# mini.net
KiCad netlist of a schematic drawn in Altium Designer
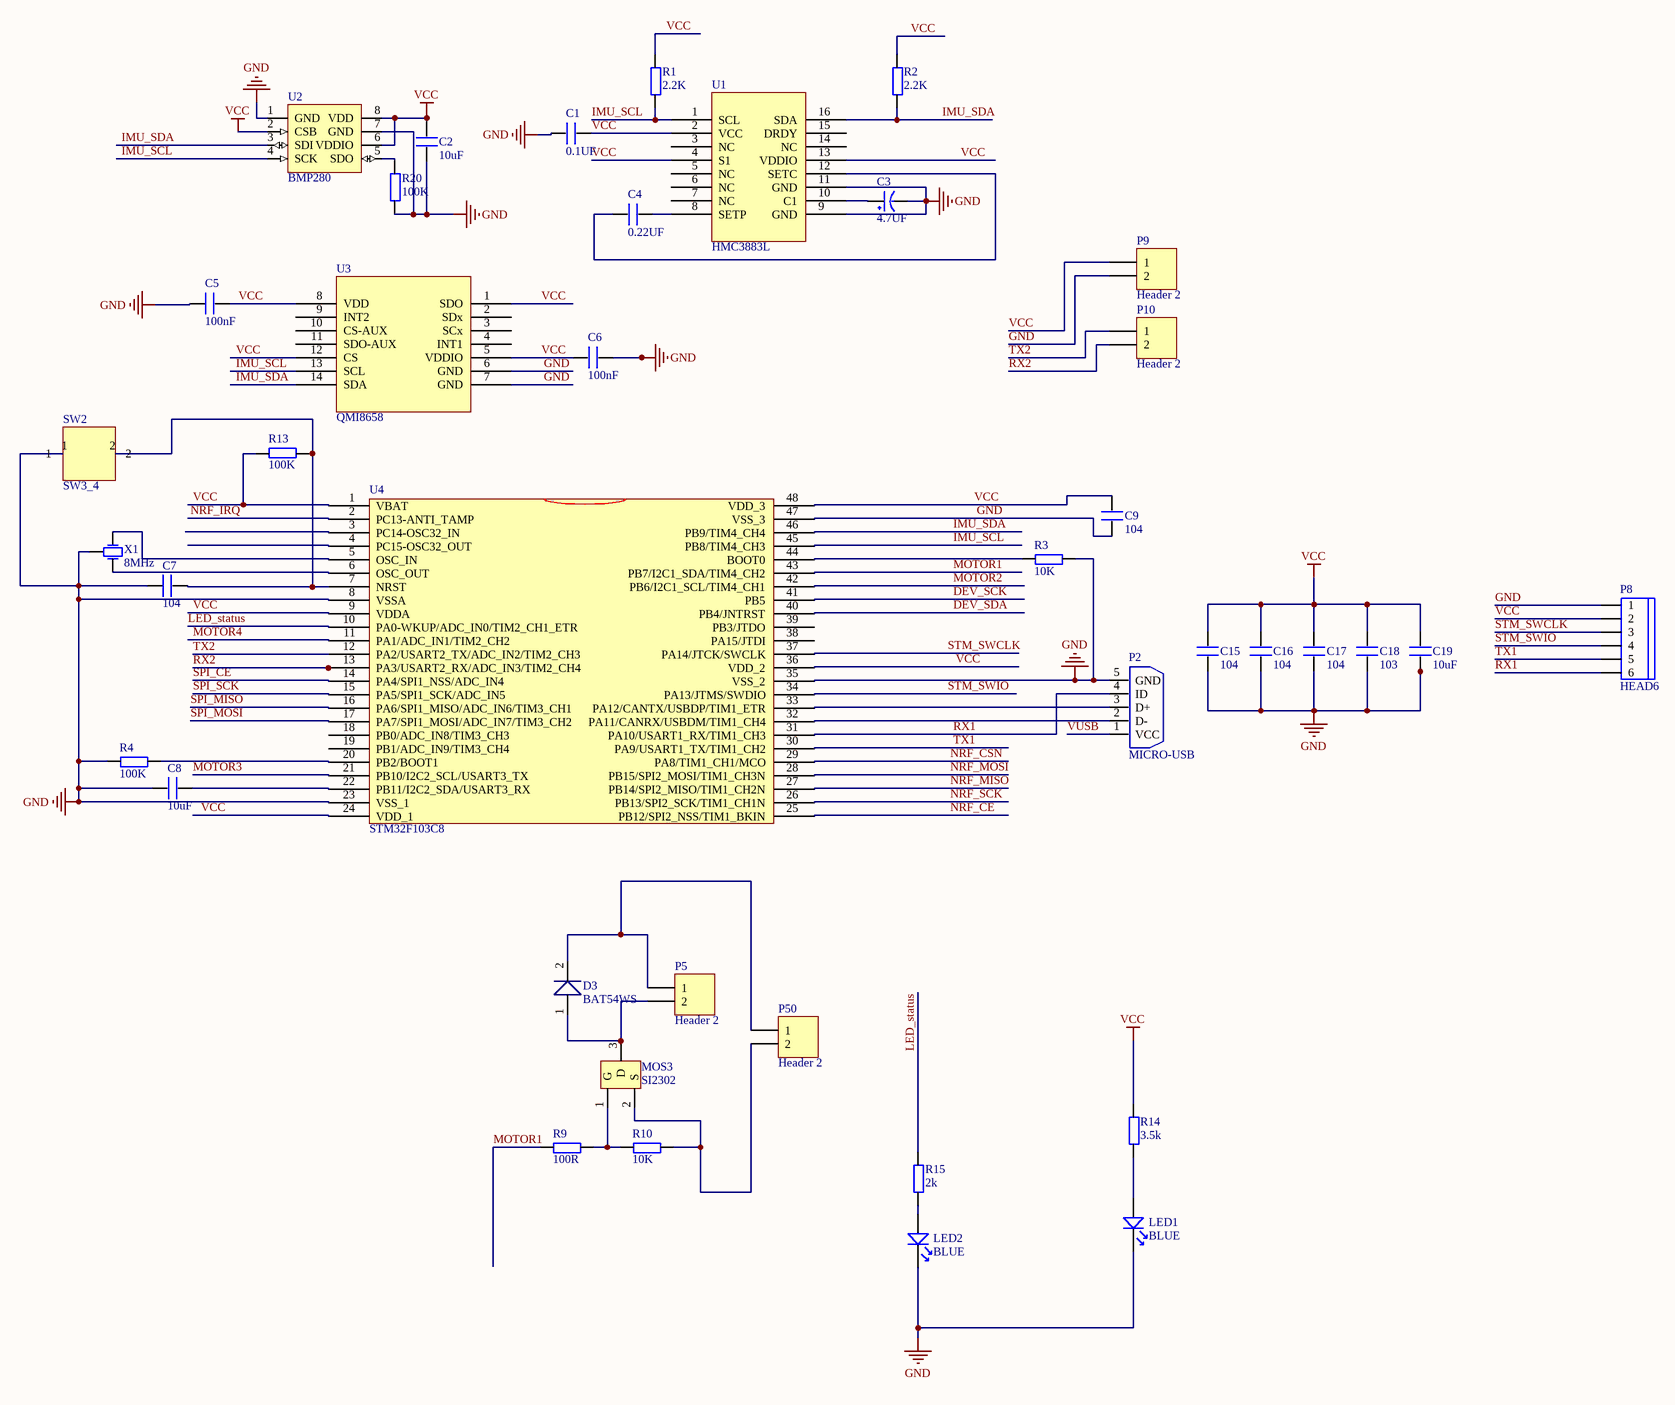
[diagram p0: mini.SchDoc]

(export (version "E")
  (design (tool "Eeschema 10.0.6"))
  (components
    (comp (ref "C1") (value "0.1UF") (footprint "0603P") (libsource (lib "MiniFly ") (part "C")))
    (comp (ref "C2") (value "10uF") (footprint "0603P") (libsource (lib "MiniFly ") (part "C")))
    (comp (ref "C3") (value "4.7UF") (footprint "C0805 钽电容") (libsource (lib "MiniFly ") (part "CAP")))
    (comp (ref "C4") (value "0.22UF") (footprint "0603P") (libsource (lib "MiniFly ") (part "C")))
    (comp (ref "C5") (value "100nF") (footprint "0603P") (libsource (lib "MiniFly ") (part "C")))
    (comp (ref "C6") (value "100nF") (footprint "0603P") (libsource (lib "MiniFly ") (part "C")))
    (comp (ref "C7") (value "104") (footprint "0603P") (libsource (lib "MiniFly ") (part "C")))
    (comp (ref "C8") (value "10uF") (footprint "0603P") (libsource (lib "MiniFly ") (part "C")))
    (comp (ref "C9") (value "104") (footprint "0603P") (libsource (lib "MiniFly ") (part "C")))
    (comp (ref "C15") (value "104") (footprint "0603P") (libsource (lib "MiniFly ") (part "C")))
    (comp (ref "C16") (value "104") (footprint "0603P") (libsource (lib "MiniFly ") (part "C")))
    (comp (ref "C17") (value "104") (footprint "0603P") (libsource (lib "MiniFly ") (part "C")))
    (comp (ref "C18") (value "103") (footprint "0603P") (libsource (lib "MiniFly ") (part "C")))
    (comp (ref "C19") (value "10uF") (footprint "0603P") (libsource (lib "MiniFly ") (part "C")))
    (comp (ref "D3")
      (value "BAT54WS")
      (footprint "SOD-323")
      (description "单肖特基二极管")
      (libsource (lib "MiniFly ") (part "BAT54"))
    )
    (comp (ref "LED1") (value "BLUE") (footprint "0603") (libsource (lib "REMOTOR") (part "LED")))
    (comp (ref "LED2") (value "BLUE") (footprint "0603") (libsource (lib "REMOTOR") (part "LED")))
    (comp (ref "MOS3")
      (value "SI2302")
      (footprint "SO-G3/C2.5")
      (description "AP2306")
      (libsource (lib "MiniFly ") (part "MOS-N"))
    )
    (comp (ref "P2")
      (value "MICRO-USB")
      (footprint "MICRO_USB5P_SOP")
      (libsource (lib "MiniFly ") (part "USB5"))
    )
    (comp (ref "P5")
      (value "Header 2")
      (footprint "HDR1X2")
      (description "Header, 2-Pin")
      (fields (field (name "PUBLISHER") "Altium Limited"))
      (libsource (lib "Miscellaneous Connectors") (part "Header 2"))
    )
    (comp (ref "P8") (value "HEAD6") (footprint "SH1.0-6P") (libsource (lib "REMOTOR") (part "HEAD6")))
    (comp (ref "P9")
      (value "Header 2")
      (footprint "HDR1X2")
      (description "Header, 2-Pin")
      (fields (field (name "PUBLISHER") "Altium Limited"))
      (libsource (lib "Miscellaneous Connectors") (part "Header 2"))
    )
    (comp (ref "P10")
      (value "Header 2")
      (footprint "HDR1X2")
      (description "Header, 2-Pin")
      (fields (field (name "PUBLISHER") "Altium Limited"))
      (libsource (lib "Miscellaneous Connectors") (part "Header 2"))
    )
    (comp (ref "P50")
      (value "Header 2")
      (footprint "HDR1X2")
      (description "Header, 2-Pin")
      (fields (field (name "PUBLISHER") "Altium Limited"))
      (libsource (lib "Miscellaneous Connectors") (part "Header 2"))
    )
    (comp (ref "R1") (value "2.2K") (footprint "MiniFly :0603P") (libsource (lib "MiniFly ") (part "R")))
    (comp (ref "R2") (value "2.2K") (footprint "0603P") (libsource (lib "MiniFly ") (part "R")))
    (comp (ref "R3") (value "10K") (footprint "0603P") (libsource (lib "MiniFly ") (part "R")))
    (comp (ref "R4") (value "100K") (footprint "MiniFly :0603P") (libsource (lib "MiniFly ") (part "R")))
    (comp (ref "R9") (value "100R") (footprint "0603P") (libsource (lib "MiniFly ") (part "R")))
    (comp (ref "R10") (value "10K") (footprint "0603P") (libsource (lib "MiniFly ") (part "R")))
    (comp (ref "R13") (value "100K") (footprint "0603P") (libsource (lib "MiniFly ") (part "R")))
    (comp (ref "R14") (value "3.5k") (footprint "0603P") (libsource (lib "MiniFly ") (part "R")))
    (comp (ref "R15") (value "2k") (footprint "0603P") (libsource (lib "MiniFly ") (part "R")))
    (comp (ref "R20") (value "100K") (footprint "0603P") (libsource (lib "MiniFly ") (part "R")))
    (comp (ref "SW2") (value "SW3_4") (footprint "SW3_4") (libsource (lib "SW") (part "SW_3_4")))
    (comp (ref "U1")
      (value "HMC3883L")
      (footprint "QFN-16PIN")
      (libsource (lib "HMC5883L") (part "HMC5883L"))
    )
    (comp (ref "U2") (value "BMP280") (footprint "LGA-8") (libsource (lib "MiniFly ") (part "BMP280")))
    (comp (ref "U3") (value "QMI8658") (footprint "14pinLGA") (libsource (lib "QMI8658") (part "QMI8658")))
    (comp (ref "U4")
      (value "STM32F103C8")
      (footprint "mTQFP48")
      (libsource (lib "REMOTOR") (part "STM32F103C6"))
    )
    (comp (ref "X1") (value "8MHz") (footprint "XTAL3215") (libsource (lib "MiniFly ") (part "XTAL-3215")))
  )
  (nets
    (net (code "1") (name "/DEV_SCK") (class "Default")
      (node (ref "U4") (pin "41") (pinfunction "PB5_41") (pintype "passive"))
    )
    (net (code "2") (name "/DEV_SDA") (class "Default")
      (node (ref "U4") (pin "40") (pinfunction "PB4/JNTRST_40") (pintype "passive"))
    )
    (net (code "3") (name "/IMU_SCL") (class "Default")
      (node (ref "R1") (pin "1") (pintype "passive"))
      (node (ref "U1") (pin "1") (pinfunction "SCL_1") (pintype "passive"))
      (node (ref "U2") (pin "4") (pinfunction "SCK_4") (pintype "input"))
      (node (ref "U3") (pin "13") (pinfunction "SCL_13") (pintype "passive"))
      (node (ref "U4") (pin "45") (pinfunction "PB8/TIM4_CH3_45") (pintype "passive"))
    )
    (net (code "4") (name "/IMU_SDA") (class "Default")
      (node (ref "R2") (pin "1") (pintype "passive"))
      (node (ref "U1") (pin "16") (pinfunction "SDA_16") (pintype "passive"))
      (node (ref "U2") (pin "3") (pinfunction "SDI_3") (pintype "bidirectional"))
      (node (ref "U3") (pin "14") (pinfunction "SDA_14") (pintype "passive"))
      (node (ref "U4") (pin "46") (pinfunction "PB9/TIM4_CH4_46") (pintype "passive"))
    )
    (net (code "5") (name "/LED_status") (class "Default")
      (node (ref "R15") (pin "2") (pintype "passive"))
      (node (ref "U4") (pin "10") (pinfunction "PA0-WKUP/ADC_IN0/TIM2_CH1_ETR_10") (pintype "passive"))
    )
    (net (code "6") (name "/MOTOR1") (class "Default")
      (node (ref "R9") (pin "1") (pintype "passive"))
      (node (ref "U4") (pin "43") (pinfunction "PB7/I2C1_SDA/TIM4_CH2_43") (pintype "passive"))
    )
    (net (code "7") (name "/MOTOR2") (class "Default")
      (node (ref "U4") (pin "42") (pinfunction "PB6/I2C1_SCL/TIM4_CH1_42") (pintype "passive"))
    )
    (net (code "8") (name "/MOTOR3") (class "Default")
      (node (ref "U4") (pin "21") (pinfunction "PB10/I2C2_SCL/USART3_TX_21") (pintype "passive"))
    )
    (net (code "9") (name "/MOTOR4") (class "Default")
      (node (ref "U4") (pin "11") (pinfunction "PA1/ADC_IN1/TIM2_CH2_11") (pintype "passive"))
    )
    (net (code "10") (name "/NRF_CE") (class "Default")
      (node (ref "U4") (pin "25") (pinfunction "PB12/SPI2_NSS/TIM1_BKIN_25") (pintype "passive"))
    )
    (net (code "11") (name "/NRF_CSN") (class "Default")
      (node (ref "U4") (pin "29") (pinfunction "PA8/TIM1_CH1/MCO_29") (pintype "passive"))
    )
    (net (code "12") (name "/NRF_IRQ") (class "Default")
      (node (ref "U4") (pin "2") (pinfunction "PC13-ANTI_TAMP_2") (pintype "passive"))
    )
    (net (code "13") (name "/NRF_MISO") (class "Default")
      (node (ref "U4") (pin "27") (pinfunction "PB14/SPI2_MISO/TIM1_CH2N_27") (pintype "passive"))
    )
    (net (code "14") (name "/NRF_MOSI") (class "Default")
      (node (ref "U4") (pin "28") (pinfunction "PB15/SPI2_MOSI/TIM1_CH3N_28") (pintype "passive"))
    )
    (net (code "15") (name "/NRF_SCK") (class "Default")
      (node (ref "U4") (pin "26") (pinfunction "PB13/SPI2_SCK/TIM1_CH1N_26") (pintype "passive"))
    )
    (net (code "16") (name "/RX1") (class "Default")
      (node (ref "P2") (pin "4") (pinfunction "ID_4") (pintype "passive"))
      (node (ref "P8") (pin "6") (pinfunction "6_6") (pintype "passive"))
      (node (ref "U4") (pin "31") (pinfunction "PA10/USART1_RX/TIM1_CH3_31") (pintype "passive"))
    )
    (net (code "17") (name "/RX2") (class "Default")
      (node (ref "P10") (pin "2") (pinfunction "2_2") (pintype "passive"))
      (node (ref "U4") (pin "13") (pinfunction "PA3/USART2_RX/ADC_IN3/TIM2_CH4_13") (pintype "passive"))
    )
    (net (code "18") (name "/SPI_CE") (class "Default")
      (node (ref "U4") (pin "14") (pinfunction "PA4/SPI1_NSS/ADC_IN4_14") (pintype "passive"))
    )
    (net (code "19") (name "/SPI_MISO") (class "Default")
      (node (ref "U4") (pin "16") (pinfunction "PA6/SPI1_MISO/ADC_IN6/TIM3_CH1_16") (pintype "passive"))
    )
    (net (code "20") (name "/SPI_MOSI") (class "Default")
      (node (ref "U4") (pin "17") (pinfunction "PA7/SPI1_MOSI/ADC_IN7/TIM3_CH2_17") (pintype "passive"))
    )
    (net (code "21") (name "/SPI_SCK") (class "Default")
      (node (ref "U4") (pin "15") (pinfunction "PA5/SPI1_SCK/ADC_IN5_15") (pintype "passive"))
    )
    (net (code "22") (name "/STM_SWCLK") (class "Default")
      (node (ref "P8") (pin "3") (pinfunction "3_3") (pintype "passive"))
      (node (ref "U4") (pin "37") (pinfunction "PA14/JTCK/SWCLK_37") (pintype "passive"))
    )
    (net (code "23") (name "/STM_SWIO") (class "Default")
      (node (ref "P8") (pin "4") (pinfunction "4_4") (pintype "passive"))
      (node (ref "U4") (pin "34") (pinfunction "PA13/JTMS/SWDIO_34") (pintype "passive"))
    )
    (net (code "24") (name "/TX1") (class "Default")
      (node (ref "P8") (pin "5") (pinfunction "5_5") (pintype "passive"))
      (node (ref "U4") (pin "30") (pinfunction "PA9/USART1_TX/TIM1_CH2_30") (pintype "passive"))
    )
    (net (code "25") (name "/TX2") (class "Default")
      (node (ref "P10") (pin "1") (pinfunction "1_1") (pintype "passive"))
      (node (ref "U4") (pin "12") (pinfunction "PA2/USART2_TX/ADC_IN2/TIM2_CH3_12") (pintype "passive"))
    )
    (net (code "26") (name "/VUSB") (class "Default")
      (node (ref "P2") (pin "1") (pinfunction "VCC_1") (pintype "passive"))
    )
    (net (code "27") (name "GND") (class "Default")
      (node (ref "C1") (pin "1") (pintype "passive"))
      (node (ref "C15") (pin "1") (pintype "passive"))
      (node (ref "C16") (pin "1") (pintype "passive"))
      (node (ref "C17") (pin "1") (pintype "passive"))
      (node (ref "C18") (pin "1") (pintype "passive"))
      (node (ref "C19") (pin "1") (pintype "passive"))
      (node (ref "C2") (pin "1") (pintype "passive"))
      (node (ref "C3") (pin "2") (pinfunction "GND_2") (pintype "passive"))
      (node (ref "C5") (pin "1") (pintype "passive"))
      (node (ref "C6") (pin "2") (pintype "passive"))
      (node (ref "C7") (pin "1") (pintype "passive"))
      (node (ref "C8") (pin "1") (pintype "passive"))
      (node (ref "C9") (pin "1") (pintype "passive"))
      (node (ref "LED1") (pin "2") (pinfunction "2_2") (pintype "passive"))
      (node (ref "LED2") (pin "2") (pinfunction "2_2") (pintype "passive"))
      (node (ref "P2") (pin "5") (pinfunction "GND_5") (pintype "passive"))
      (node (ref "P8") (pin "1") (pinfunction "1_1") (pintype "passive"))
      (node (ref "P9") (pin "2") (pinfunction "2_2") (pintype "passive"))
      (node (ref "R20") (pin "1") (pintype "passive"))
      (node (ref "R3") (pin "2") (pintype "passive"))
      (node (ref "R4") (pin "1") (pintype "passive"))
      (node (ref "SW2") (pin "1") (pinfunction "1_1") (pintype "passive"))
      (node (ref "U1") (pin "11") (pinfunction "GND_11") (pintype "passive"))
      (node (ref "U1") (pin "9") (pinfunction "GND_9") (pintype "passive"))
      (node (ref "U2") (pin "1") (pinfunction "GND_1") (pintype "passive"))
      (node (ref "U2") (pin "7") (pinfunction "GND_7") (pintype "power_in"))
      (node (ref "U3") (pin "6") (pinfunction "GND_6") (pintype "passive"))
      (node (ref "U3") (pin "7") (pinfunction "GND_7") (pintype "passive"))
      (node (ref "U4") (pin "23") (pinfunction "VSS_1_23") (pintype "passive"))
      (node (ref "U4") (pin "35") (pinfunction "VSS_2_35") (pintype "passive"))
      (node (ref "U4") (pin "47") (pinfunction "VSS_3_47") (pintype "passive"))
      (node (ref "U4") (pin "8") (pinfunction "VSSA_8") (pintype "passive"))
      (node (ref "X1") (pin "2") (pinfunction "GND_2") (pintype "passive"))
    )
    (net (code "28") (name "Net-(C3-VCC)") (class "Default")
      (node (ref "C3") (pin "1") (pinfunction "VCC_1") (pintype "passive"))
      (node (ref "U1") (pin "10") (pinfunction "C1_10") (pintype "passive"))
    )
    (net (code "29") (name "Net-(D3-Pad2)") (class "Default")
      (node (ref "D3") (pin "2") (pinfunction "2_2") (pintype "passive"))
      (node (ref "P5") (pin "1") (pinfunction "1_1") (pintype "passive"))
      (node (ref "P50") (pin "1") (pinfunction "1_1") (pintype "passive"))
    )
    (net (code "30") (name "Net-(LED1-Pad1)") (class "Default")
      (node (ref "LED1") (pin "1") (pinfunction "1_1") (pintype "passive"))
      (node (ref "R14") (pin "1") (pintype "passive"))
    )
    (net (code "31") (name "Net-(LED2-Pad1)") (class "Default")
      (node (ref "LED2") (pin "1") (pinfunction "1_1") (pintype "passive"))
      (node (ref "R15") (pin "1") (pintype "passive"))
    )
    (net (code "32") (name "Net-(MOS3-D)") (class "Default")
      (node (ref "D3") (pin "1") (pinfunction "1_1") (pintype "passive"))
      (node (ref "MOS3") (pin "3") (pinfunction "D_3") (pintype "passive"))
      (node (ref "P5") (pin "2") (pinfunction "2_2") (pintype "passive"))
    )
    (net (code "33") (name "Net-(MOS3-G)") (class "Default")
      (node (ref "MOS3") (pin "1") (pinfunction "G_1") (pintype "passive"))
      (node (ref "R10") (pin "1") (pintype "passive"))
      (node (ref "R9") (pin "2") (pintype "passive"))
    )
    (net (code "34") (name "Net-(MOS3-S)") (class "Default")
      (node (ref "MOS3") (pin "2") (pinfunction "S_2") (pintype "passive"))
      (node (ref "P50") (pin "2") (pinfunction "2_2") (pintype "passive"))
      (node (ref "R10") (pin "2") (pintype "passive"))
    )
    (net (code "35") (name "Net-(P2-D+)") (class "Default")
      (node (ref "P2") (pin "3") (pinfunction "D+_3") (pintype "passive"))
      (node (ref "U4") (pin "33") (pinfunction "PA12/CANTX/USBDP/TIM1_ETR_33") (pintype "passive"))
    )
    (net (code "36") (name "Net-(P2-D-)") (class "Default")
      (node (ref "P2") (pin "2") (pinfunction "D-_2") (pintype "passive"))
      (node (ref "U4") (pin "32") (pinfunction "PA11/CANRX/USBDM/TIM1_CH4_32") (pintype "passive"))
    )
    (net (code "37") (name "Net-(U1-SETC)") (class "Default")
      (node (ref "C4") (pin "1") (pintype "passive"))
      (node (ref "U1") (pin "12") (pinfunction "SETC_12") (pintype "passive"))
    )
    (net (code "38") (name "Net-(U1-SETP)") (class "Default")
      (node (ref "C4") (pin "2") (pintype "passive"))
      (node (ref "U1") (pin "8") (pinfunction "SETP_8") (pintype "passive"))
    )
    (net (code "39") (name "Net-(U2-SDO)") (class "Default")
      (node (ref "R20") (pin "2") (pintype "passive"))
      (node (ref "U2") (pin "5") (pinfunction "SDO_5") (pintype "bidirectional"))
    )
    (net (code "40") (name "Net-(U4-BOOT0)") (class "Default")
      (node (ref "R3") (pin "1") (pintype "passive"))
      (node (ref "U4") (pin "44") (pinfunction "BOOT0_44") (pintype "passive"))
    )
    (net (code "41") (name "Net-(U4-NRST)") (class "Default")
      (node (ref "C7") (pin "2") (pintype "passive"))
      (node (ref "R13") (pin "1") (pintype "passive"))
      (node (ref "SW2") (pin "2") (pinfunction "2_2") (pintype "passive"))
      (node (ref "U4") (pin "7") (pinfunction "NRST_7") (pintype "passive"))
    )
    (net (code "42") (name "Net-(U4-OSC_IN)") (class "Default")
      (node (ref "U4") (pin "5") (pinfunction "OSC_IN_5") (pintype "passive"))
      (node (ref "X1") (pin "1") (pinfunction "OSC1_1") (pintype "passive"))
    )
    (net (code "43") (name "Net-(U4-OSC_OUT)") (class "Default")
      (node (ref "U4") (pin "6") (pinfunction "OSC_OUT_6") (pintype "passive"))
      (node (ref "X1") (pin "3") (pinfunction "OSC2_3") (pintype "passive"))
    )
    (net (code "44") (name "Net-(U4-PB2{slash}BOOT1)") (class "Default")
      (node (ref "R4") (pin "2") (pintype "passive"))
      (node (ref "U4") (pin "20") (pinfunction "PB2/BOOT1_20") (pintype "passive"))
    )
    (net (code "45") (name "Net-(U4-PB11{slash}I2C2_SDA{slash}USART3_RX)") (class "Default")
      (node (ref "C8") (pin "2") (pintype "passive"))
      (node (ref "U4") (pin "22") (pinfunction "PB11/I2C2_SDA/USART3_RX_22") (pintype "passive"))
    )
    (net (code "46") (name "VCC") (class "Default")
      (node (ref "C1") (pin "2") (pintype "passive"))
      (node (ref "C15") (pin "2") (pintype "passive"))
      (node (ref "C16") (pin "2") (pintype "passive"))
      (node (ref "C17") (pin "2") (pintype "passive"))
      (node (ref "C18") (pin "2") (pintype "passive"))
      (node (ref "C19") (pin "2") (pintype "passive"))
      (node (ref "C2") (pin "2") (pintype "passive"))
      (node (ref "C5") (pin "2") (pintype "passive"))
      (node (ref "C6") (pin "1") (pintype "passive"))
      (node (ref "C9") (pin "2") (pintype "passive"))
      (node (ref "P8") (pin "2") (pinfunction "2_2") (pintype "passive"))
      (node (ref "P9") (pin "1") (pinfunction "1_1") (pintype "passive"))
      (node (ref "R1") (pin "2") (pintype "passive"))
      (node (ref "R13") (pin "2") (pintype "passive"))
      (node (ref "R14") (pin "2") (pintype "passive"))
      (node (ref "R2") (pin "2") (pintype "passive"))
      (node (ref "U1") (pin "13") (pinfunction "VDDIO_13") (pintype "passive"))
      (node (ref "U1") (pin "2") (pinfunction "VCC_2") (pintype "passive"))
      (node (ref "U1") (pin "4") (pinfunction "S1_4") (pintype "passive"))
      (node (ref "U2") (pin "2") (pinfunction "CSB_2") (pintype "input"))
      (node (ref "U2") (pin "6") (pinfunction "VDDIO_6") (pintype "power_in"))
      (node (ref "U2") (pin "8") (pinfunction "VDD_8") (pintype "power_in"))
      (node (ref "U3") (pin "1") (pinfunction "SDO_1") (pintype "passive"))
      (node (ref "U3") (pin "12") (pinfunction "CS_12") (pintype "passive"))
      (node (ref "U3") (pin "5") (pinfunction "VDDIO_5") (pintype "passive"))
      (node (ref "U3") (pin "8") (pinfunction "VDD_8") (pintype "passive"))
      (node (ref "U4") (pin "1") (pinfunction "VBAT_1") (pintype "passive"))
      (node (ref "U4") (pin "24") (pinfunction "VDD_1_24") (pintype "passive"))
      (node (ref "U4") (pin "36") (pinfunction "VDD_2_36") (pintype "passive"))
      (node (ref "U4") (pin "48") (pinfunction "VDD_3_48") (pintype "passive"))
      (node (ref "U4") (pin "9") (pinfunction "VDDA_9") (pintype "passive"))
    )
    (net (code "47") (name "unconnected-(U1-DRDY-Pad15)") (class "Default")
      (node (ref "U1") (pin "15") (pinfunction "DRDY_15") (pintype "passive"))
    )
    (net (code "48") (name "unconnected-(U1-NC-Pad3)") (class "Default")
      (node (ref "U1") (pin "3") (pinfunction "NC_3") (pintype "passive"))
    )
    (net (code "49") (name "unconnected-(U1-NC-Pad5)") (class "Default")
      (node (ref "U1") (pin "5") (pinfunction "NC_5") (pintype "passive"))
    )
    (net (code "50") (name "unconnected-(U1-NC-Pad6)") (class "Default")
      (node (ref "U1") (pin "6") (pinfunction "NC_6") (pintype "passive"))
    )
    (net (code "51") (name "unconnected-(U1-NC-Pad7)") (class "Default")
      (node (ref "U1") (pin "7") (pinfunction "NC_7") (pintype "passive"))
    )
    (net (code "52") (name "unconnected-(U1-NC-Pad14)") (class "Default")
      (node (ref "U1") (pin "14") (pinfunction "NC_14") (pintype "passive"))
    )
    (net (code "53") (name "unconnected-(U3-CS-AUX-Pad10)") (class "Default")
      (node (ref "U3") (pin "10") (pinfunction "CS-AUX_10") (pintype "passive"))
    )
    (net (code "54") (name "unconnected-(U3-INT1-Pad4)") (class "Default")
      (node (ref "U3") (pin "4") (pinfunction "INT1_4") (pintype "passive"))
    )
    (net (code "55") (name "unconnected-(U3-INT2-Pad9)") (class "Default")
      (node (ref "U3") (pin "9") (pinfunction "INT2_9") (pintype "passive"))
    )
    (net (code "56") (name "unconnected-(U3-SCx-Pad3)") (class "Default")
      (node (ref "U3") (pin "3") (pinfunction "SCx_3") (pintype "passive"))
    )
    (net (code "57") (name "unconnected-(U3-SDO-AUX-Pad11)") (class "Default")
      (node (ref "U3") (pin "11") (pinfunction "SDO-AUX_11") (pintype "passive"))
    )
    (net (code "58") (name "unconnected-(U3-SDx-Pad2)") (class "Default")
      (node (ref "U3") (pin "2") (pinfunction "SDx_2") (pintype "passive"))
    )
    (net (code "59") (name "unconnected-(U4-PA15{slash}JTDI-Pad38)") (class "Default")
      (node (ref "U4") (pin "38") (pinfunction "PA15/JTDI_38") (pintype "passive"))
    )
    (net (code "60") (name "unconnected-(U4-PB0{slash}ADC_IN8{slash}TIM3_CH3-Pad18)") (class "Default")
      (node (ref "U4") (pin "18") (pinfunction "PB0/ADC_IN8/TIM3_CH3_18") (pintype "passive"))
    )
    (net (code "61") (name "unconnected-(U4-PB1{slash}ADC_IN9{slash}TIM3_CH4-Pad19)") (class "Default")
      (node (ref "U4") (pin "19") (pinfunction "PB1/ADC_IN9/TIM3_CH4_19") (pintype "passive"))
    )
    (net (code "62") (name "unconnected-(U4-PB3{slash}JTDO-Pad39)") (class "Default")
      (node (ref "U4") (pin "39") (pinfunction "PB3/JTDO_39") (pintype "passive"))
    )
    (net (code "63") (name "unconnected-(U4-PC14-OSC32_IN-Pad3)") (class "Default")
      (node (ref "U4") (pin "3") (pinfunction "PC14-OSC32_IN_3") (pintype "passive"))
    )
    (net (code "64") (name "unconnected-(U4-PC15-OSC32_OUT-Pad4)") (class "Default")
      (node (ref "U4") (pin "4") (pinfunction "PC15-OSC32_OUT_4") (pintype "passive"))
    )
  )
)
